# Sitara_IO_Bank_45.net
KiCad netlist of a schematic drawn in Altium Designer
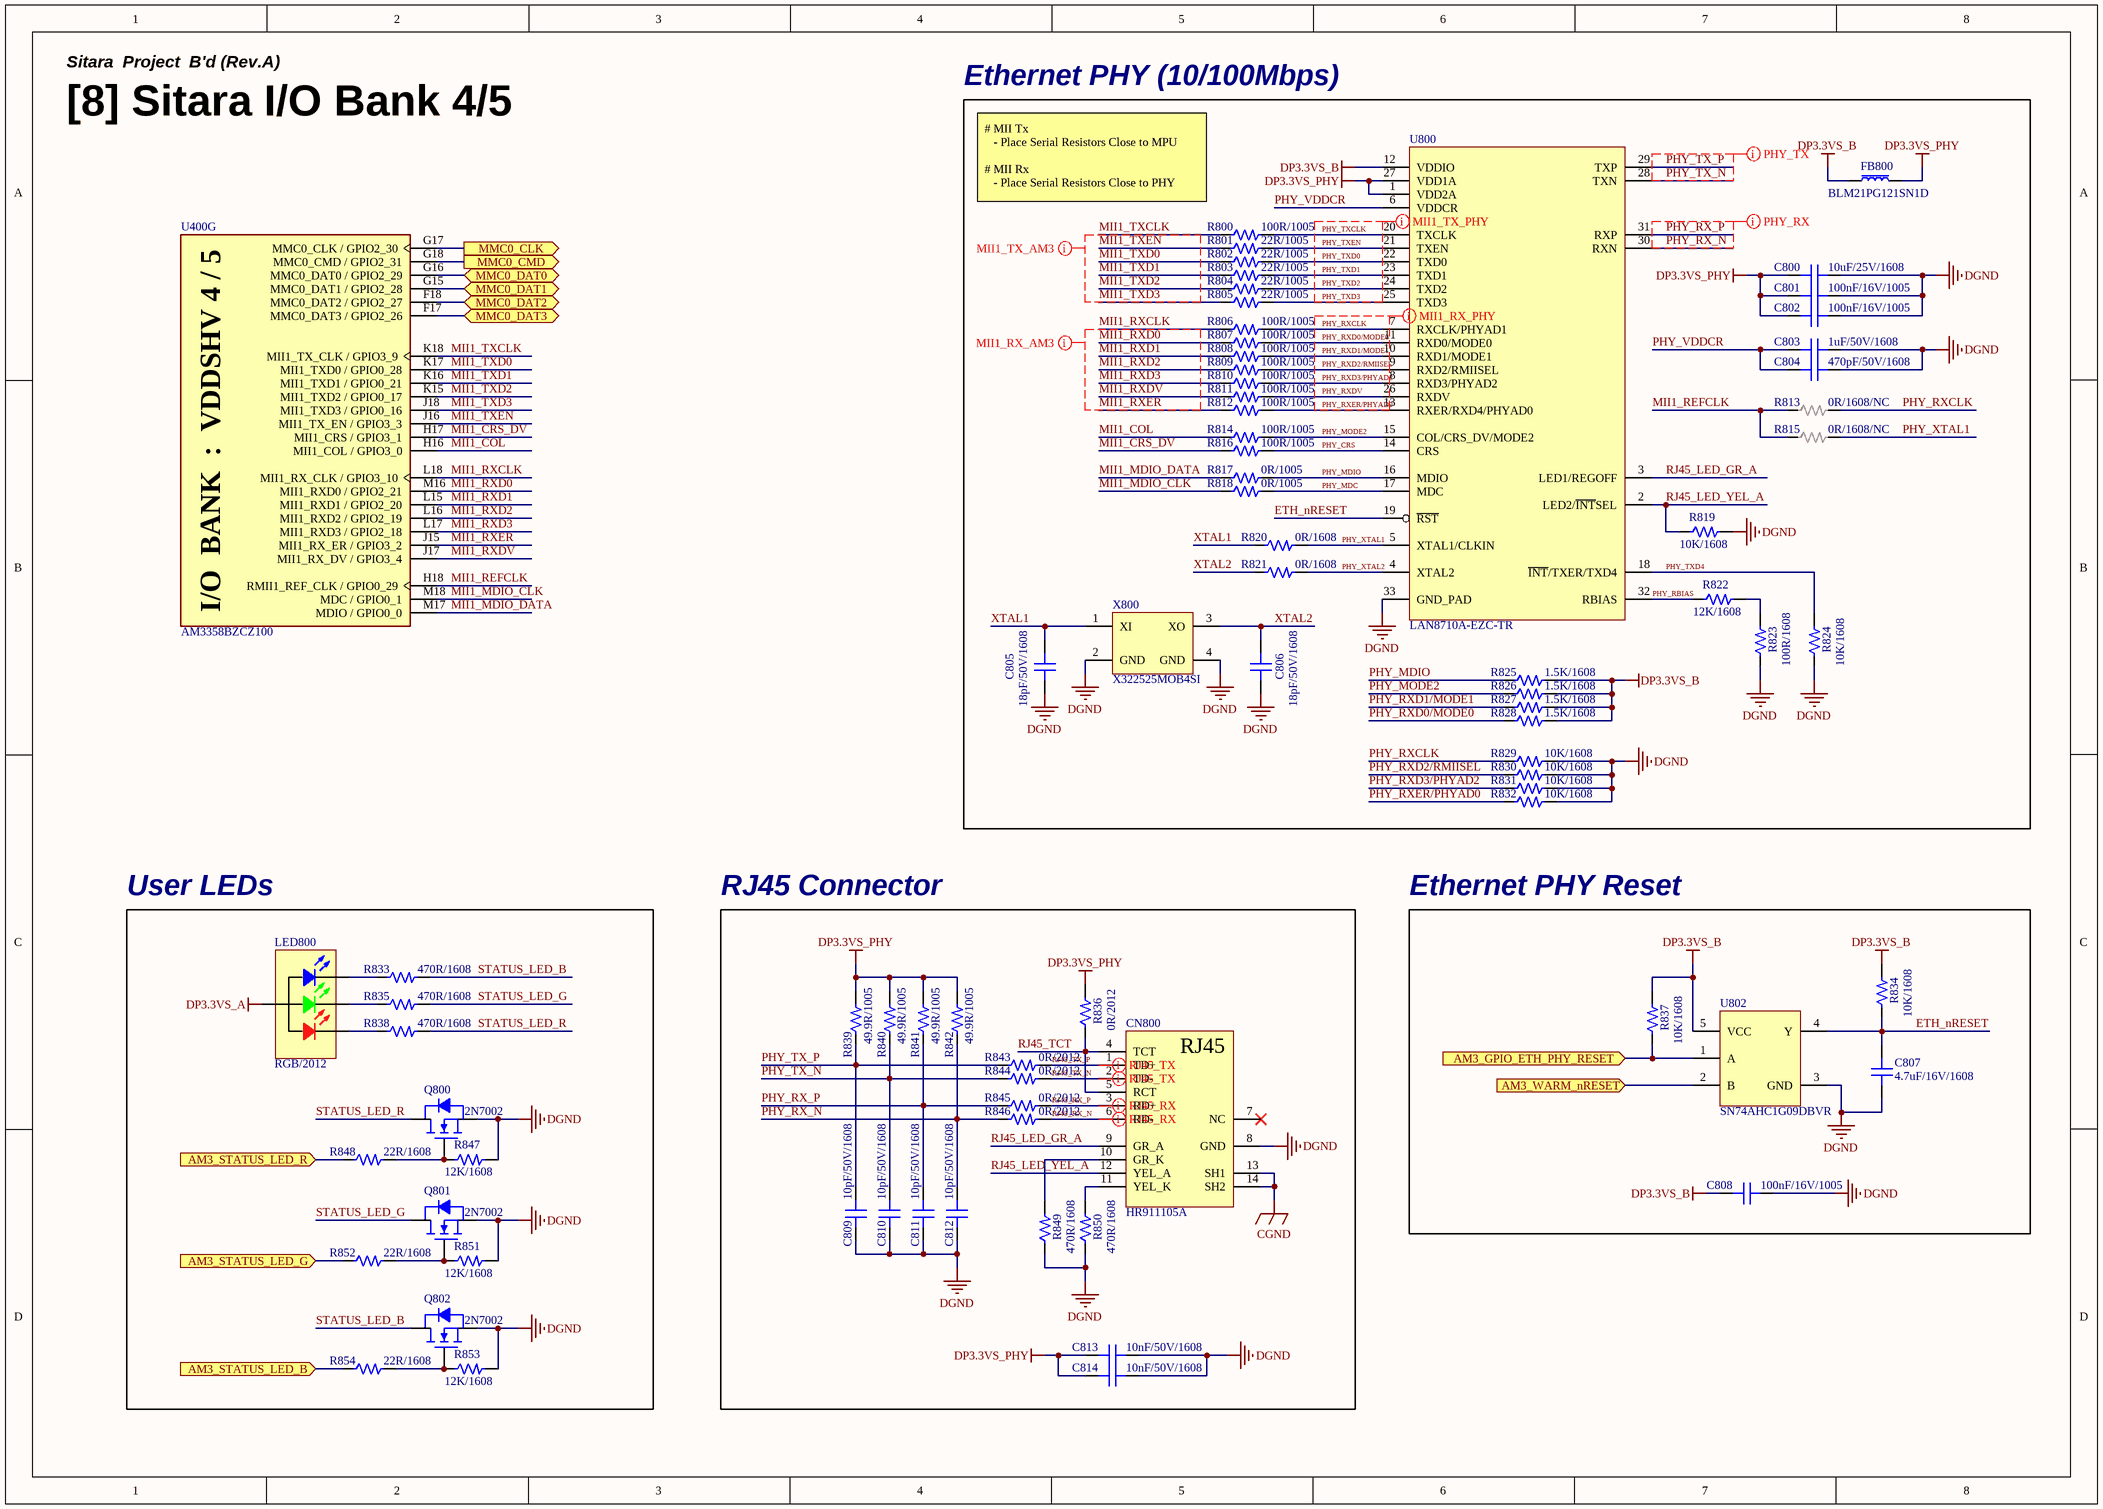
[diagram p0: Sitara_IO_Bank_45.SchDoc]

(export (version "E")
  (design (tool "Eeschema 10.0.6"))
  (components
    (comp (ref "C800")
      (value "10uF/25V/1608")
      (footprint "CAP 1608 (0603_INCH)")
      (description "Ceramic CAP_10uF/25V/1608")
      (fields (field (name "LCSC PART #") "C96446"))
      (libsource (lib "Arkx") (part "CAP_10uF/25V/1608"))
    )
    (comp (ref "C801")
      (value "100nF/16V/1005")
      (footprint "CAP 1005 (0402_INCH)")
      (description "Ceramic CAP_100nF/16V/1005")
      (fields (field (name "LCSC PART #") "C1525"))
      (libsource (lib "Arkx") (part "CAP_100nF/16V/1005"))
    )
    (comp (ref "C802")
      (value "100nF/16V/1005")
      (footprint "CAP 1005 (0402_INCH)")
      (description "Ceramic CAP_100nF/16V/1005")
      (fields (field (name "LCSC PART #") "C1525"))
      (libsource (lib "Arkx") (part "CAP_100nF/16V/1005"))
    )
    (comp (ref "C803")
      (value "1uF/50V/1608")
      (footprint "CAP 1608 (0603_INCH)")
      (description "Ceramic CAP_1uF/50V/1608")
      (fields (field (name "LCSC PART #") "C15849"))
      (libsource (lib "Arkx") (part "CAP_1uF/50V/1608"))
    )
    (comp (ref "C804")
      (value "470pF/50V/1608")
      (footprint "CAP 1608 (0603_INCH)")
      (description "Ceramic CAP_470pF/50V/1608")
      (fields (field (name "LCSC PART #") "C1620"))
      (libsource (lib "Arkx") (part "CAP_470pF/50V/1608"))
    )
    (comp (ref "C805")
      (value "18pF/50V/1608")
      (footprint "CAP 1608 (0603_INCH)")
      (description "Ceramic CAP_18pF/50V/1608")
      (fields (field (name "LCSC PART #") "C1647"))
      (libsource (lib "Arkx") (part "CAP_18pF/50V/1608"))
    )
    (comp (ref "C806")
      (value "18pF/50V/1608")
      (footprint "CAP 1608 (0603_INCH)")
      (description "Ceramic CAP_18pF/50V/1608")
      (fields (field (name "LCSC PART #") "C1647"))
      (libsource (lib "Arkx") (part "CAP_18pF/50V/1608"))
    )
    (comp (ref "C807")
      (value "4.7uF/16V/1608")
      (footprint "CAP 1608 (0603_INCH)")
      (description "Ceramic CAP_4.7uF/16V/1608")
      (fields (field (name "LCSC PART #") "C19666"))
      (libsource (lib "Arkx") (part "CAP_4.7uF/16V/1608"))
    )
    (comp (ref "C808")
      (value "100nF/16V/1005")
      (footprint "CAP 1005 (0402_INCH)")
      (description "Ceramic CAP_100nF/16V/1005")
      (fields (field (name "LCSC PART #") "C1525"))
      (libsource (lib "Arkx") (part "CAP_100nF/16V/1005"))
    )
    (comp (ref "C809")
      (value "10pF/50V/1608")
      (footprint "CAP 1608 (0603_INCH)")
      (description "Ceramic CAP_10pF/50V/1608")
      (fields (field (name "LCSC PART #") "C1634"))
      (libsource (lib "Arkx") (part "CAP_10pF/50V/1608"))
    )
    (comp (ref "C810")
      (value "10pF/50V/1608")
      (footprint "CAP 1608 (0603_INCH)")
      (description "Ceramic CAP_10pF/50V/1608")
      (fields (field (name "LCSC PART #") "C1634"))
      (libsource (lib "Arkx") (part "CAP_10pF/50V/1608"))
    )
    (comp (ref "C811")
      (value "10pF/50V/1608")
      (footprint "CAP 1608 (0603_INCH)")
      (description "Ceramic CAP_10pF/50V/1608")
      (fields (field (name "LCSC PART #") "C1634"))
      (libsource (lib "Arkx") (part "CAP_10pF/50V/1608"))
    )
    (comp (ref "C812")
      (value "10pF/50V/1608")
      (footprint "CAP 1608 (0603_INCH)")
      (description "Ceramic CAP_10pF/50V/1608")
      (fields (field (name "LCSC PART #") "C1634"))
      (libsource (lib "Arkx") (part "CAP_10pF/50V/1608"))
    )
    (comp (ref "C813")
      (value "10nF/50V/1608")
      (footprint "CAP 1608 (0603_INCH)")
      (description "Ceramic CAP_10nF/50V/1608")
      (fields (field (name "LCSC PART #") "C57112"))
      (libsource (lib "Arkx") (part "CAP_10nF/50V/1608"))
    )
    (comp (ref "C814")
      (value "10nF/50V/1608")
      (footprint "CAP 1608 (0603_INCH)")
      (description "Ceramic CAP_10nF/50V/1608")
      (fields (field (name "LCSC PART #") "C57112"))
      (libsource (lib "Arkx") (part "CAP_10nF/50V/1608"))
    )
    (comp (ref "CN800")
      (value "HR911105A")
      (footprint "CON_RJ45")
      (description "RJ45Receptacle 1 WithLED Plugin Ethernet Connectors / Modular Connectors (RJ45 RJ11) ROHS")
      (fields (field (name "LCSC PART #") "C12074"))
      (libsource (lib "Arkx") (part "CON_RJ45_HR911105A"))
    )
    (comp (ref "FB800")
      (value "BLM21PG121SN1D")
      (footprint "FB 2012 (0805_inch)")
      (description "3A 1 30mΩ 120Ω@100MHz ±25% 0805  Ferrite Beads ROHS")
      (fields (field (name "LCSC PART #") "C79382"))
      (libsource (lib "Arkx") (part "FB_BLM21PG121SN1D"))
    )
    (comp (ref "LED800")
      (value "RGB/2012")
      (footprint "LED MHT170RGBCT")
      (fields (field (name "LCSC PART #") "C2962094"))
      (libsource (lib "Arkx") (part "LED_RGB_MHT170RGBCT"))
    )
    (comp (ref "Q800")
      (value "2N7002")
      (footprint "SOT 23-3 (DIODES INCORPORATED)")
      (description "60V 115mA 200mW 7.5Ω@10V,500mA N Channel SOT-23  MOSFETs ROHS")
      (fields (field (name "LCSC PART #") "C8545"))
      (libsource (lib "Arkx") (part "FET_2N7002"))
    )
    (comp (ref "Q801")
      (value "2N7002")
      (footprint "SOT 23-3 (DIODES INCORPORATED)")
      (description "60V 115mA 200mW 7.5Ω@10V,500mA N Channel SOT-23  MOSFETs ROHS")
      (fields (field (name "LCSC PART #") "C8545"))
      (libsource (lib "Arkx") (part "FET_2N7002"))
    )
    (comp (ref "Q802")
      (value "2N7002")
      (footprint "SOT 23-3 (DIODES INCORPORATED)")
      (description "60V 115mA 200mW 7.5Ω@10V,500mA N Channel SOT-23  MOSFETs ROHS")
      (fields (field (name "LCSC PART #") "C8545"))
      (libsource (lib "Arkx") (part "FET_2N7002"))
    )
    (comp (ref "R800")
      (value "100R/1005")
      (footprint "RES 1005 (0402_inch)")
      (description "RES_100R/1005/62.5mW")
      (fields (field (name "LCSC PART #") "C25076"))
      (libsource (lib "Arkx") (part "RES_100R/1005/62.5mW"))
    )
    (comp (ref "R801")
      (value "22R/1005")
      (footprint "RES 1005 (0402_inch)")
      (description "RES_22R/1005/62.5mW")
      (fields (field (name "LCSC PART #") "C25092"))
      (libsource (lib "Arkx") (part "RES_22R/1005/62.5mW"))
    )
    (comp (ref "R802")
      (value "22R/1005")
      (footprint "RES 1005 (0402_inch)")
      (description "RES_22R/1005/62.5mW")
      (fields (field (name "LCSC PART #") "C25092"))
      (libsource (lib "Arkx") (part "RES_22R/1005/62.5mW"))
    )
    (comp (ref "R803")
      (value "22R/1005")
      (footprint "RES 1005 (0402_inch)")
      (description "RES_22R/1005/62.5mW")
      (fields (field (name "LCSC PART #") "C25092"))
      (libsource (lib "Arkx") (part "RES_22R/1005/62.5mW"))
    )
    (comp (ref "R804")
      (value "22R/1005")
      (footprint "RES 1005 (0402_inch)")
      (description "RES_22R/1005/62.5mW")
      (fields (field (name "LCSC PART #") "C25092"))
      (libsource (lib "Arkx") (part "RES_22R/1005/62.5mW"))
    )
    (comp (ref "R805")
      (value "22R/1005")
      (footprint "RES 1005 (0402_inch)")
      (description "RES_22R/1005/62.5mW")
      (fields (field (name "LCSC PART #") "C25092"))
      (libsource (lib "Arkx") (part "RES_22R/1005/62.5mW"))
    )
    (comp (ref "R806")
      (value "100R/1005")
      (footprint "RES 1005 (0402_inch)")
      (description "RES_100R/1005/62.5mW")
      (fields (field (name "LCSC PART #") "C25076"))
      (libsource (lib "Arkx") (part "RES_100R/1005/62.5mW"))
    )
    (comp (ref "R807")
      (value "100R/1005")
      (footprint "RES 1005 (0402_inch)")
      (description "RES_100R/1005/62.5mW")
      (fields (field (name "LCSC PART #") "C25076"))
      (libsource (lib "Arkx") (part "RES_100R/1005/62.5mW"))
    )
    (comp (ref "R808")
      (value "100R/1005")
      (footprint "RES 1005 (0402_inch)")
      (description "RES_100R/1005/62.5mW")
      (fields (field (name "LCSC PART #") "C25076"))
      (libsource (lib "Arkx") (part "RES_100R/1005/62.5mW"))
    )
    (comp (ref "R809")
      (value "100R/1005")
      (footprint "RES 1005 (0402_inch)")
      (description "RES_100R/1005/62.5mW")
      (fields (field (name "LCSC PART #") "C25076"))
      (libsource (lib "Arkx") (part "RES_100R/1005/62.5mW"))
    )
    (comp (ref "R810")
      (value "100R/1005")
      (footprint "RES 1005 (0402_inch)")
      (description "RES_100R/1005/62.5mW")
      (fields (field (name "LCSC PART #") "C25076"))
      (libsource (lib "Arkx") (part "RES_100R/1005/62.5mW"))
    )
    (comp (ref "R811")
      (value "100R/1005")
      (footprint "RES 1005 (0402_inch)")
      (description "RES_100R/1005/62.5mW")
      (fields (field (name "LCSC PART #") "C25076"))
      (libsource (lib "Arkx") (part "RES_100R/1005/62.5mW"))
    )
    (comp (ref "R812")
      (value "100R/1005")
      (footprint "RES 1005 (0402_inch)")
      (description "RES_100R/1005/62.5mW")
      (fields (field (name "LCSC PART #") "C25076"))
      (libsource (lib "Arkx") (part "RES_100R/1005/62.5mW"))
    )
    (comp (ref "R813")
      (value "0R/1608/NC")
      (footprint "RES 1608 (0603_inch)/NC")
      (description "0R/1608/0.1W/NC")
      (libsource (lib "Arkx") (part "RES_NC_0R/1608/0.1W"))
    )
    (comp (ref "R814")
      (value "100R/1005")
      (footprint "RES 1005 (0402_inch)")
      (description "RES_100R/1005/62.5mW")
      (fields (field (name "LCSC PART #") "C25076"))
      (libsource (lib "Arkx") (part "RES_100R/1005/62.5mW"))
    )
    (comp (ref "R815")
      (value "0R/1608/NC")
      (footprint "RES 1608 (0603_inch)/NC")
      (description "0R/1608/0.1W/NC")
      (libsource (lib "Arkx") (part "RES_NC_0R/1608/0.1W"))
    )
    (comp (ref "R816")
      (value "100R/1005")
      (footprint "RES 1005 (0402_inch)")
      (description "RES_100R/1005/62.5mW")
      (fields (field (name "LCSC PART #") "C25076"))
      (libsource (lib "Arkx") (part "RES_100R/1005/62.5mW"))
    )
    (comp (ref "R817")
      (value "0R/1005")
      (footprint "RES 1005 (0402_inch)")
      (description "RES_0R/1005/62.5mW")
      (fields (field (name "LCSC PART #") "C17168"))
      (libsource (lib "Arkx") (part "RES_0R/1005/62.5mW"))
    )
    (comp (ref "R818")
      (value "0R/1005")
      (footprint "RES 1005 (0402_inch)")
      (description "RES_0R/1005/62.5mW")
      (fields (field (name "LCSC PART #") "C17168"))
      (libsource (lib "Arkx") (part "RES_0R/1005/62.5mW"))
    )
    (comp (ref "R819")
      (value "10K/1608")
      (footprint "RES 1608 (0603_inch)")
      (description "RES_10K/1608/0.1W")
      (fields (field (name "LCSC PART #") "C25804"))
      (libsource (lib "Arkx") (part "RES_10K/1608/0.1W"))
    )
    (comp (ref "R820")
      (value "0R/1608")
      (footprint "RES 1608 (0603_inch)")
      (description "RES_0R/1608/0.1W")
      (fields (field (name "LCSC PART #") "C21189"))
      (libsource (lib "Arkx") (part "RES_0R/1608/0.1W"))
    )
    (comp (ref "R821")
      (value "0R/1608")
      (footprint "RES 1608 (0603_inch)")
      (description "RES_0R/1608/0.1W")
      (fields (field (name "LCSC PART #") "C21189"))
      (libsource (lib "Arkx") (part "RES_0R/1608/0.1W"))
    )
    (comp (ref "R822")
      (value "12K/1608")
      (footprint "RES 1608 (0603_inch)")
      (description "RES_12K/1608/0.1W")
      (fields (field (name "LCSC PART #") "C22790"))
      (libsource (lib "Arkx") (part "RES_12K/1608/0.1W"))
    )
    (comp (ref "R823")
      (value "100R/1608")
      (footprint "RES 1608 (0603_inch)")
      (description "RES_100R/1608/0.1W")
      (fields (field (name "LCSC PART #") "C22775"))
      (libsource (lib "Arkx") (part "RES_100R/1608/0.1W"))
    )
    (comp (ref "R824")
      (value "10K/1608")
      (footprint "RES 1608 (0603_inch)")
      (description "RES_10K/1608/0.1W")
      (fields (field (name "LCSC PART #") "C25804"))
      (libsource (lib "Arkx") (part "RES_10K/1608/0.1W"))
    )
    (comp (ref "R825")
      (value "1.5K/1608")
      (footprint "RES 1608 (0603_inch)")
      (description "RES_1.5K/1608/0.1W")
      (fields (field (name "LCSC PART #") "C22843"))
      (libsource (lib "Arkx") (part "RES_1.5K/1608/0.1W"))
    )
    (comp (ref "R826")
      (value "1.5K/1608")
      (footprint "RES 1608 (0603_inch)")
      (description "RES_1.5K/1608/0.1W")
      (fields (field (name "LCSC PART #") "C22843"))
      (libsource (lib "Arkx") (part "RES_1.5K/1608/0.1W"))
    )
    (comp (ref "R827")
      (value "1.5K/1608")
      (footprint "RES 1608 (0603_inch)")
      (description "RES_1.5K/1608/0.1W")
      (fields (field (name "LCSC PART #") "C22843"))
      (libsource (lib "Arkx") (part "RES_1.5K/1608/0.1W"))
    )
    (comp (ref "R828")
      (value "1.5K/1608")
      (footprint "RES 1608 (0603_inch)")
      (description "RES_1.5K/1608/0.1W")
      (fields (field (name "LCSC PART #") "C22843"))
      (libsource (lib "Arkx") (part "RES_1.5K/1608/0.1W"))
    )
    (comp (ref "R829")
      (value "10K/1608")
      (footprint "RES 1608 (0603_inch)")
      (description "RES_10K/1608/0.1W")
      (fields (field (name "LCSC PART #") "C25804"))
      (libsource (lib "Arkx") (part "RES_10K/1608/0.1W"))
    )
    (comp (ref "R830")
      (value "10K/1608")
      (footprint "RES 1608 (0603_inch)")
      (description "RES_10K/1608/0.1W")
      (fields (field (name "LCSC PART #") "C25804"))
      (libsource (lib "Arkx") (part "RES_10K/1608/0.1W"))
    )
    (comp (ref "R831")
      (value "10K/1608")
      (footprint "RES 1608 (0603_inch)")
      (description "RES_10K/1608/0.1W")
      (fields (field (name "LCSC PART #") "C25804"))
      (libsource (lib "Arkx") (part "RES_10K/1608/0.1W"))
    )
    (comp (ref "R832")
      (value "10K/1608")
      (footprint "RES 1608 (0603_inch)")
      (description "RES_10K/1608/0.1W")
      (fields (field (name "LCSC PART #") "C25804"))
      (libsource (lib "Arkx") (part "RES_10K/1608/0.1W"))
    )
    (comp (ref "R833")
      (value "470R/1608")
      (footprint "RES 1608 (0603_inch)")
      (description "RES_470R/1608/0.1W")
      (fields (field (name "LCSC PART #") "C23179"))
      (libsource (lib "Arkx") (part "RES_470R/1608/0.1W"))
    )
    (comp (ref "R834")
      (value "10K/1608")
      (footprint "RES 1608 (0603_inch)")
      (description "RES_10K/1608/0.1W")
      (fields (field (name "LCSC PART #") "C25804"))
      (libsource (lib "Arkx") (part "RES_10K/1608/0.1W"))
    )
    (comp (ref "R835")
      (value "470R/1608")
      (footprint "RES 1608 (0603_inch)")
      (description "RES_470R/1608/0.1W")
      (fields (field (name "LCSC PART #") "C23179"))
      (libsource (lib "Arkx") (part "RES_470R/1608/0.1W"))
    )
    (comp (ref "R836")
      (value "0R/2012")
      (footprint "RES 2012 (0805_inch)")
      (description "RES_0R/2012/0.125W")
      (fields (field (name "LCSC PART #") "C17477"))
      (libsource (lib "Arkx") (part "RES_0R/2012/0.125W"))
    )
    (comp (ref "R837")
      (value "10K/1608")
      (footprint "RES 1608 (0603_inch)")
      (description "RES_10K/1608/0.1W")
      (fields (field (name "LCSC PART #") "C25804"))
      (libsource (lib "Arkx") (part "RES_10K/1608/0.1W"))
    )
    (comp (ref "R838")
      (value "470R/1608")
      (footprint "RES 1608 (0603_inch)")
      (description "RES_470R/1608/0.1W")
      (fields (field (name "LCSC PART #") "C23179"))
      (libsource (lib "Arkx") (part "RES_470R/1608/0.1W"))
    )
    (comp (ref "R839")
      (value "49.9R/1005")
      (footprint "RES 1005 (0402_inch)")
      (description "RES_49.9R/1005/62.5mW")
      (fields (field (name "LCSC PART #") "C25120"))
      (libsource (lib "Arkx") (part "RES_49.9R/1005/62.5mW"))
    )
    (comp (ref "R840")
      (value "49.9R/1005")
      (footprint "RES 1005 (0402_inch)")
      (description "RES_49.9R/1005/62.5mW")
      (fields (field (name "LCSC PART #") "C25120"))
      (libsource (lib "Arkx") (part "RES_49.9R/1005/62.5mW"))
    )
    (comp (ref "R841")
      (value "49.9R/1005")
      (footprint "RES 1005 (0402_inch)")
      (description "RES_49.9R/1005/62.5mW")
      (fields (field (name "LCSC PART #") "C25120"))
      (libsource (lib "Arkx") (part "RES_49.9R/1005/62.5mW"))
    )
    (comp (ref "R842")
      (value "49.9R/1005")
      (footprint "RES 1005 (0402_inch)")
      (description "RES_49.9R/1005/62.5mW")
      (fields (field (name "LCSC PART #") "C25120"))
      (libsource (lib "Arkx") (part "RES_49.9R/1005/62.5mW"))
    )
    (comp (ref "R843")
      (value "0R/2012")
      (footprint "RES 2012 (0805_inch)")
      (description "RES_0R/2012/0.125W")
      (fields (field (name "LCSC PART #") "C17477"))
      (libsource (lib "Arkx") (part "RES_0R/2012/0.125W"))
    )
    (comp (ref "R844")
      (value "0R/2012")
      (footprint "RES 2012 (0805_inch)")
      (description "RES_0R/2012/0.125W")
      (fields (field (name "LCSC PART #") "C17477"))
      (libsource (lib "Arkx") (part "RES_0R/2012/0.125W"))
    )
    (comp (ref "R845")
      (value "0R/2012")
      (footprint "RES 2012 (0805_inch)")
      (description "RES_0R/2012/0.125W")
      (fields (field (name "LCSC PART #") "C17477"))
      (libsource (lib "Arkx") (part "RES_0R/2012/0.125W"))
    )
    (comp (ref "R846")
      (value "0R/2012")
      (footprint "RES 2012 (0805_inch)")
      (description "RES_0R/2012/0.125W")
      (fields (field (name "LCSC PART #") "C17477"))
      (libsource (lib "Arkx") (part "RES_0R/2012/0.125W"))
    )
    (comp (ref "R847")
      (value "12K/1608")
      (footprint "RES 1608 (0603_inch)")
      (description "RES_12K/1608/0.1W")
      (fields (field (name "LCSC PART #") "C22790"))
      (libsource (lib "Arkx") (part "RES_12K/1608/0.1W"))
    )
    (comp (ref "R848")
      (value "22R/1608")
      (footprint "RES 1608 (0603_inch)")
      (description "RES_22R/1608/0.1W")
      (fields (field (name "LCSC PART #") "C23345"))
      (libsource (lib "Arkx") (part "RES_22R/1608/0.1W"))
    )
    (comp (ref "R849")
      (value "470R/1608")
      (footprint "RES 1608 (0603_inch)")
      (description "RES_470R/1608/0.1W")
      (fields (field (name "LCSC PART #") "C23179"))
      (libsource (lib "Arkx") (part "RES_470R/1608/0.1W"))
    )
    (comp (ref "R850")
      (value "470R/1608")
      (footprint "RES 1608 (0603_inch)")
      (description "RES_470R/1608/0.1W")
      (fields (field (name "LCSC PART #") "C23179"))
      (libsource (lib "Arkx") (part "RES_470R/1608/0.1W"))
    )
    (comp (ref "R851")
      (value "12K/1608")
      (footprint "RES 1608 (0603_inch)")
      (description "RES_12K/1608/0.1W")
      (fields (field (name "LCSC PART #") "C22790"))
      (libsource (lib "Arkx") (part "RES_12K/1608/0.1W"))
    )
    (comp (ref "R852")
      (value "22R/1608")
      (footprint "RES 1608 (0603_inch)")
      (description "RES_22R/1608/0.1W")
      (fields (field (name "LCSC PART #") "C23345"))
      (libsource (lib "Arkx") (part "RES_22R/1608/0.1W"))
    )
    (comp (ref "R853")
      (value "12K/1608")
      (footprint "RES 1608 (0603_inch)")
      (description "RES_12K/1608/0.1W")
      (fields (field (name "LCSC PART #") "C22790"))
      (libsource (lib "Arkx") (part "RES_12K/1608/0.1W"))
    )
    (comp (ref "R854")
      (value "22R/1608")
      (footprint "RES 1608 (0603_inch)")
      (description "RES_22R/1608/0.1W")
      (fields (field (name "LCSC PART #") "C23345"))
      (libsource (lib "Arkx") (part "RES_22R/1608/0.1W"))
    )
    (comp (ref "U400")
      (value "AM3358BZCZ100")
      (footprint "IC_SOC_AM3358BZCZ100")
      (description "ARM® Cortex®-A8 Microprocessor IC Sitara™ 1 Core, 32-Bit 1.0GHz 324-NFBGA (15x15)")
      (fields (field (name "LCSC PART #") "C73932"))
      (libsource (lib "Arkx") (part "IC_SOC_AM3358BZCZ100"))
    )
    (comp (ref "U800")
      (value "LAN8710A-EZC-TR")
      (footprint "IC_QFN-32 (5x5)")
      (description "4/4 Transceiver Full MII, RMII 32-QFN (5x5)")
      (fields (field (name "LCSC PART #") "C46185"))
      (libsource (lib "Arkx") (part "IC_ETH_LAN8710A-EZC-TR"))
    )
    (comp (ref "U802")
      (value "SN74AHC1G09DBVR")
      (footprint "SOT-23-5 (TI DBV PACKAGE)")
      (description "AND Gate IC 1 Channel Open Drain SOT-23-5")
      (fields (field (name "LCSC PART #") "C840099"))
      (libsource (lib "Arkx") (part "IC_AND_SN74AHC1G09DBVR"))
    )
    (comp (ref "X800")
      (value "X322525MOB4SI")
      (footprint "OSC_SMD_3.2x2.5(YXC)")
      (description "25MHz Surface Mount Crystal 12pF ±10ppm ±20ppm SMD3225-4P Crystals ROHS")
      (fields (field (name "LCSC PART #") "C9006"))
      (libsource (lib "Arkx") (part "XTAL_25MHz_X322525MOB4SI"))
    )
  )
  (nets
    (net (code "1") (name "/AM3_GPIO_ETH_PHY_RESET") (class "Default")
      (node (ref "R837") (pin "1") (pinfunction "1_1") (pintype "passive"))
      (node (ref "U802") (pin "1") (pinfunction "A_1") (pintype "passive"))
    )
    (net (code "2") (name "/AM3_STATUS_LED_B") (class "Default")
      (node (ref "R854") (pin "1") (pinfunction "1_1") (pintype "passive"))
    )
    (net (code "3") (name "/AM3_STATUS_LED_G") (class "Default")
      (node (ref "R852") (pin "1") (pinfunction "1_1") (pintype "passive"))
    )
    (net (code "4") (name "/AM3_STATUS_LED_R") (class "Default")
      (node (ref "R848") (pin "1") (pinfunction "1_1") (pintype "passive"))
    )
    (net (code "5") (name "/AM3_WARM_nRESET") (class "Default")
      (node (ref "U802") (pin "2") (pinfunction "B_2") (pintype "passive"))
    )
    (net (code "6") (name "/ETH_nRESET") (class "Default")
      (node (ref "C807") (pin "2") (pinfunction "2_2") (pintype "passive"))
      (node (ref "R834") (pin "1") (pinfunction "1_1") (pintype "passive"))
      (node (ref "U800") (pin "19") (pinfunction "~{RST}_19") (pintype "passive"))
      (node (ref "U802") (pin "4") (pinfunction "Y_4") (pintype "passive"))
    )
    (net (code "7") (name "/MII1_COL") (class "Default")
      (node (ref "R814") (pin "1") (pinfunction "1_1") (pintype "passive"))
      (node (ref "U400") (pin "H16") (pinfunction "MII1_COL_/_GPIO3_0_H16") (pintype "passive"))
    )
    (net (code "8") (name "/MII1_CRS_DV") (class "Default")
      (node (ref "R816") (pin "1") (pinfunction "1_1") (pintype "passive"))
      (node (ref "U400") (pin "H17") (pinfunction "MII1_CRS_/_GPIO3_1_H17") (pintype "passive"))
    )
    (net (code "9") (name "/MII1_MDIO_CLK") (class "Default")
      (node (ref "R818") (pin "1") (pinfunction "1_1") (pintype "passive"))
      (node (ref "U400") (pin "M18") (pinfunction "MDC_/_GPIO0_1_M18") (pintype "passive"))
    )
    (net (code "10") (name "/MII1_MDIO_DATA") (class "Default")
      (node (ref "R817") (pin "1") (pinfunction "1_1") (pintype "passive"))
      (node (ref "U400") (pin "M17") (pinfunction "MDIO_/_GPIO0_0_M17") (pintype "passive"))
    )
    (net (code "11") (name "/MII1_REFCLK") (class "Default")
      (node (ref "R813") (pin "1") (pinfunction "1_1") (pintype "passive"))
      (node (ref "R815") (pin "1") (pinfunction "1_1") (pintype "passive"))
      (node (ref "U400") (pin "H18") (pinfunction "RMII1_REF_CLK_/_GPIO0_29_H18") (pintype "passive"))
    )
    (net (code "12") (name "/MII1_RXCLK") (class "Default")
      (node (ref "R806") (pin "1") (pinfunction "1_1") (pintype "passive"))
      (node (ref "U400") (pin "L18") (pinfunction "MII1_RX_CLK_/_GPIO3_10_L18") (pintype "passive"))
    )
    (net (code "13") (name "/MII1_RXD0") (class "Default")
      (node (ref "R807") (pin "1") (pinfunction "1_1") (pintype "passive"))
      (node (ref "U400") (pin "M16") (pinfunction "MII1_RXD0_/_GPIO2_21_M16") (pintype "passive"))
    )
    (net (code "14") (name "/MII1_RXD1") (class "Default")
      (node (ref "R808") (pin "1") (pinfunction "1_1") (pintype "passive"))
      (node (ref "U400") (pin "L15") (pinfunction "MII1_RXD1_/_GPIO2_20_L15") (pintype "passive"))
    )
    (net (code "15") (name "/MII1_RXD2") (class "Default")
      (node (ref "R809") (pin "1") (pinfunction "1_1") (pintype "passive"))
      (node (ref "U400") (pin "L16") (pinfunction "MII1_RXD2_/_GPIO2_19_L16") (pintype "passive"))
    )
    (net (code "16") (name "/MII1_RXD3") (class "Default")
      (node (ref "R810") (pin "1") (pinfunction "1_1") (pintype "passive"))
      (node (ref "U400") (pin "L17") (pinfunction "MII1_RXD3_/_GPIO2_18_L17") (pintype "passive"))
    )
    (net (code "17") (name "/MII1_RXDV") (class "Default")
      (node (ref "R811") (pin "1") (pinfunction "1_1") (pintype "passive"))
      (node (ref "U400") (pin "J17") (pinfunction "MII1_RX_DV_/_GPIO3_4_J17") (pintype "passive"))
    )
    (net (code "18") (name "/MII1_RXER") (class "Default")
      (node (ref "R812") (pin "1") (pinfunction "1_1") (pintype "passive"))
      (node (ref "U400") (pin "J15") (pinfunction "MII1_RX_ER_/_GPIO3_2_J15") (pintype "passive"))
    )
    (net (code "19") (name "/MII1_TXCLK") (class "Default")
      (node (ref "R800") (pin "1") (pinfunction "1_1") (pintype "passive"))
      (node (ref "U400") (pin "K18") (pinfunction "MII1_TX_CLK_/_GPIO3_9_K18") (pintype "passive"))
    )
    (net (code "20") (name "/MII1_TXD0") (class "Default")
      (node (ref "R802") (pin "1") (pinfunction "1_1") (pintype "passive"))
      (node (ref "U400") (pin "K17") (pinfunction "MII1_TXD0_/_GPIO0_28_K17") (pintype "passive"))
    )
    (net (code "21") (name "/MII1_TXD1") (class "Default")
      (node (ref "R803") (pin "1") (pinfunction "1_1") (pintype "passive"))
      (node (ref "U400") (pin "K16") (pinfunction "MII1_TXD1_/_GPIO0_21_K16") (pintype "passive"))
    )
    (net (code "22") (name "/MII1_TXD2") (class "Default")
      (node (ref "R804") (pin "1") (pinfunction "1_1") (pintype "passive"))
      (node (ref "U400") (pin "K15") (pinfunction "MII1_TXD2_/_GPIO0_17_K15") (pintype "passive"))
    )
    (net (code "23") (name "/MII1_TXD3") (class "Default")
      (node (ref "R805") (pin "1") (pinfunction "1_1") (pintype "passive"))
      (node (ref "U400") (pin "J18") (pinfunction "MII1_TXD3_/_GPIO0_16_J18") (pintype "passive"))
    )
    (net (code "24") (name "/MII1_TXEN") (class "Default")
      (node (ref "R801") (pin "1") (pinfunction "1_1") (pintype "passive"))
      (node (ref "U400") (pin "J16") (pinfunction "MII1_TX_EN_/_GPIO3_3_J16") (pintype "passive"))
    )
    (net (code "25") (name "/MMC0_CLK") (class "Default")
      (node (ref "U400") (pin "G17") (pinfunction "MMC0_CLK_/_GPIO2_30_G17") (pintype "passive"))
    )
    (net (code "26") (name "/MMC0_CMD") (class "Default")
      (node (ref "U400") (pin "G18") (pinfunction "MMC0_CMD_/_GPIO2_31_G18") (pintype "passive"))
    )
    (net (code "27") (name "/MMC0_DAT0") (class "Default")
      (node (ref "U400") (pin "G16") (pinfunction "MMC0_DAT0_/_GPIO2_29_G16") (pintype "passive"))
    )
    (net (code "28") (name "/MMC0_DAT1") (class "Default")
      (node (ref "U400") (pin "G15") (pinfunction "MMC0_DAT1_/_GPIO2_28_G15") (pintype "passive"))
    )
    (net (code "29") (name "/MMC0_DAT2") (class "Default")
      (node (ref "U400") (pin "F18") (pinfunction "MMC0_DAT2_/_GPIO2_27_F18") (pintype "passive"))
    )
    (net (code "30") (name "/MMC0_DAT3") (class "Default")
      (node (ref "U400") (pin "F17") (pinfunction "MMC0_DAT3_/_GPIO2_26_F17") (pintype "passive"))
    )
    (net (code "31") (name "/PHY_CRS") (class "Default")
      (node (ref "R816") (pin "2") (pinfunction "2_2") (pintype "passive"))
      (node (ref "U800") (pin "14") (pinfunction "CRS_14") (pintype "passive"))
    )
    (net (code "32") (name "/PHY_MDC") (class "Default")
      (node (ref "R818") (pin "2") (pinfunction "2_2") (pintype "passive"))
      (node (ref "U800") (pin "17") (pinfunction "MDC_17") (pintype "passive"))
    )
    (net (code "33") (name "/PHY_MDIO") (class "Default")
      (node (ref "R817") (pin "2") (pinfunction "2_2") (pintype "passive"))
      (node (ref "R825") (pin "1") (pinfunction "1_1") (pintype "passive"))
      (node (ref "U800") (pin "16") (pinfunction "MDIO_16") (pintype "passive"))
    )
    (net (code "34") (name "/PHY_MODE2") (class "Default")
      (node (ref "R814") (pin "2") (pinfunction "2_2") (pintype "passive"))
      (node (ref "R826") (pin "1") (pinfunction "1_1") (pintype "passive"))
      (node (ref "U800") (pin "15") (pinfunction "COL/CRS_DV/MODE2_15") (pintype "passive"))
    )
    (net (code "35") (name "/PHY_RBIAS") (class "Default")
      (node (ref "R822") (pin "1") (pinfunction "1_1") (pintype "passive"))
      (node (ref "U800") (pin "32") (pinfunction "RBIAS_32") (pintype "passive"))
    )
    (net (code "36") (name "/PHY_RXCLK") (class "Default")
      (node (ref "R806") (pin "2") (pinfunction "2_2") (pintype "passive"))
      (node (ref "R813") (pin "2") (pinfunction "2_2") (pintype "passive"))
      (node (ref "R829") (pin "1") (pinfunction "1_1") (pintype "passive"))
      (node (ref "U800") (pin "7") (pinfunction "RXCLK/PHYAD1_7") (pintype "passive"))
    )
    (net (code "37") (name "/PHY_RXD0{slash}MODE0") (class "Default")
      (node (ref "R807") (pin "2") (pinfunction "2_2") (pintype "passive"))
      (node (ref "R828") (pin "1") (pinfunction "1_1") (pintype "passive"))
      (node (ref "U800") (pin "11") (pinfunction "RXD0/MODE0_11") (pintype "passive"))
    )
    (net (code "38") (name "/PHY_RXD1{slash}MODE1") (class "Default")
      (node (ref "R808") (pin "2") (pinfunction "2_2") (pintype "passive"))
      (node (ref "R827") (pin "1") (pinfunction "1_1") (pintype "passive"))
      (node (ref "U800") (pin "10") (pinfunction "RXD1/MODE1_10") (pintype "passive"))
    )
    (net (code "39") (name "/PHY_RXD2{slash}RMIISEL") (class "Default")
      (node (ref "R809") (pin "2") (pinfunction "2_2") (pintype "passive"))
      (node (ref "R830") (pin "1") (pinfunction "1_1") (pintype "passive"))
      (node (ref "U800") (pin "9") (pinfunction "RXD2/RMIISEL_9") (pintype "passive"))
    )
    (net (code "40") (name "/PHY_RXD3{slash}PHYAD2") (class "Default")
      (node (ref "R810") (pin "2") (pinfunction "2_2") (pintype "passive"))
      (node (ref "R831") (pin "1") (pinfunction "1_1") (pintype "passive"))
      (node (ref "U800") (pin "8") (pinfunction "RXD3/PHYAD2_8") (pintype "passive"))
    )
    (net (code "41") (name "/PHY_RXDV") (class "Default")
      (node (ref "R811") (pin "2") (pinfunction "2_2") (pintype "passive"))
      (node (ref "U800") (pin "26") (pinfunction "RXDV_26") (pintype "passive"))
    )
    (net (code "42") (name "/PHY_RXER{slash}PHYAD0") (class "Default")
      (node (ref "R812") (pin "2") (pinfunction "2_2") (pintype "passive"))
      (node (ref "R832") (pin "1") (pinfunction "1_1") (pintype "passive"))
      (node (ref "U800") (pin "13") (pinfunction "RXER/RXD4/PHYAD0_13") (pintype "passive"))
    )
    (net (code "43") (name "/PHY_RX_N") (class "Default")
      (node (ref "C812") (pin "2") (pinfunction "2_2") (pintype "passive"))
      (node (ref "R842") (pin "1") (pinfunction "1_1") (pintype "passive"))
      (node (ref "R846") (pin "1") (pinfunction "1_1") (pintype "passive"))
      (node (ref "U800") (pin "30") (pinfunction "RXN_30") (pintype "passive"))
    )
    (net (code "44") (name "/PHY_RX_P") (class "Default")
      (node (ref "C811") (pin "2") (pinfunction "2_2") (pintype "passive"))
      (node (ref "R841") (pin "1") (pinfunction "1_1") (pintype "passive"))
      (node (ref "R845") (pin "1") (pinfunction "1_1") (pintype "passive"))
      (node (ref "U800") (pin "31") (pinfunction "RXP_31") (pintype "passive"))
    )
    (net (code "45") (name "/PHY_TXCLK") (class "Default")
      (node (ref "R800") (pin "2") (pinfunction "2_2") (pintype "passive"))
      (node (ref "U800") (pin "20") (pinfunction "TXCLK_20") (pintype "passive"))
    )
    (net (code "46") (name "/PHY_TXD0") (class "Default")
      (node (ref "R802") (pin "2") (pinfunction "2_2") (pintype "passive"))
      (node (ref "U800") (pin "22") (pinfunction "TXD0_22") (pintype "passive"))
    )
    (net (code "47") (name "/PHY_TXD1") (class "Default")
      (node (ref "R803") (pin "2") (pinfunction "2_2") (pintype "passive"))
      (node (ref "U800") (pin "23") (pinfunction "TXD1_23") (pintype "passive"))
    )
    (net (code "48") (name "/PHY_TXD2") (class "Default")
      (node (ref "R804") (pin "2") (pinfunction "2_2") (pintype "passive"))
      (node (ref "U800") (pin "24") (pinfunction "TXD2_24") (pintype "passive"))
    )
    (net (code "49") (name "/PHY_TXD3") (class "Default")
      (node (ref "R805") (pin "2") (pinfunction "2_2") (pintype "passive"))
      (node (ref "U800") (pin "25") (pinfunction "TXD3_25") (pintype "passive"))
    )
    (net (code "50") (name "/PHY_TXD4") (class "Default")
      (node (ref "R824") (pin "2") (pinfunction "2_2") (pintype "passive"))
      (node (ref "U800") (pin "18") (pinfunction "~{INT}/TXER/TXD4_18") (pintype "passive"))
    )
    (net (code "51") (name "/PHY_TXEN") (class "Default")
      (node (ref "R801") (pin "2") (pinfunction "2_2") (pintype "passive"))
      (node (ref "U800") (pin "21") (pinfunction "TXEN_21") (pintype "passive"))
    )
    (net (code "52") (name "/PHY_TX_N") (class "Default")
      (node (ref "C810") (pin "2") (pinfunction "2_2") (pintype "passive"))
      (node (ref "R840") (pin "1") (pinfunction "1_1") (pintype "passive"))
      (node (ref "R844") (pin "1") (pinfunction "1_1") (pintype "passive"))
      (node (ref "U800") (pin "28") (pinfunction "TXN_28") (pintype "passive"))
    )
    (net (code "53") (name "/PHY_TX_P") (class "Default")
      (node (ref "C809") (pin "2") (pinfunction "2_2") (pintype "passive"))
      (node (ref "R839") (pin "1") (pinfunction "1_1") (pintype "passive"))
      (node (ref "R843") (pin "1") (pinfunction "1_1") (pintype "passive"))
      (node (ref "U800") (pin "29") (pinfunction "TXP_29") (pintype "passive"))
    )
    (net (code "54") (name "/PHY_VDDCR") (class "Default")
      (node (ref "C803") (pin "1") (pinfunction "1_1") (pintype "passive"))
      (node (ref "C804") (pin "1") (pinfunction "1_1") (pintype "passive"))
      (node (ref "U800") (pin "6") (pinfunction "VDDCR_6") (pintype "passive"))
    )
    (net (code "55") (name "/PHY_XTAL1") (class "Default")
      (node (ref "R815") (pin "2") (pinfunction "2_2") (pintype "passive"))
      (node (ref "R820") (pin "2") (pinfunction "2_2") (pintype "passive"))
      (node (ref "U800") (pin "5") (pinfunction "XTAL1/CLKIN_5") (pintype "passive"))
    )
    (net (code "56") (name "/PHY_XTAL2") (class "Default")
      (node (ref "R821") (pin "2") (pinfunction "2_2") (pintype "passive"))
      (node (ref "U800") (pin "4") (pinfunction "XTAL2_4") (pintype "passive"))
    )
    (net (code "57") (name "/RJ45_LED_GR_A") (class "Default")
      (node (ref "CN800") (pin "9") (pinfunction "GR_A_9") (pintype "passive"))
      (node (ref "U800") (pin "3") (pinfunction "LED1/REGOFF_3") (pintype "passive"))
    )
    (net (code "58") (name "/RJ45_LED_YEL_A") (class "Default")
      (node (ref "CN800") (pin "12") (pinfunction "YEL_A_12") (pintype "passive"))
      (node (ref "R819") (pin "1") (pinfunction "1_1") (pintype "passive"))
      (node (ref "U800") (pin "2") (pinfunction "LED2/~{INT}SEL_2") (pintype "passive"))
    )
    (net (code "59") (name "/RJ45_RX_N") (class "Default")
      (node (ref "CN800") (pin "6") (pinfunction "RD-_6") (pintype "passive"))
      (node (ref "R846") (pin "2") (pinfunction "2_2") (pintype "passive"))
    )
    (net (code "60") (name "/RJ45_RX_P") (class "Default")
      (node (ref "CN800") (pin "3") (pinfunction "RD+_3") (pintype "passive"))
      (node (ref "R845") (pin "2") (pinfunction "2_2") (pintype "passive"))
    )
    (net (code "61") (name "/RJ45_TCT") (class "Default")
      (node (ref "CN800") (pin "4") (pinfunction "TCT_4") (pintype "passive"))
      (node (ref "CN800") (pin "5") (pinfunction "RCT_5") (pintype "passive"))
      (node (ref "R836") (pin "1") (pinfunction "1_1") (pintype "passive"))
    )
    (net (code "62") (name "/RJ45_TX_N") (class "Default")
      (node (ref "CN800") (pin "2") (pinfunction "TD-_2") (pintype "passive"))
      (node (ref "R844") (pin "2") (pinfunction "2_2") (pintype "passive"))
    )
    (net (code "63") (name "/RJ45_TX_P") (class "Default")
      (node (ref "CN800") (pin "1") (pinfunction "TD+_1") (pintype "passive"))
      (node (ref "R843") (pin "2") (pinfunction "2_2") (pintype "passive"))
    )
    (net (code "64") (name "/STATUS_LED_B") (class "Default")
      (node (ref "Q802") (pin "3") (pinfunction "D_3") (pintype "passive"))
      (node (ref "R833") (pin "2") (pinfunction "2_2") (pintype "passive"))
    )
    (net (code "65") (name "/STATUS_LED_G") (class "Default")
      (node (ref "Q801") (pin "3") (pinfunction "D_3") (pintype "passive"))
      (node (ref "R835") (pin "2") (pinfunction "2_2") (pintype "passive"))
    )
    (net (code "66") (name "/STATUS_LED_R") (class "Default")
      (node (ref "Q800") (pin "3") (pinfunction "D_3") (pintype "passive"))
      (node (ref "R838") (pin "2") (pinfunction "2_2") (pintype "passive"))
    )
    (net (code "67") (name "/XTAL1") (class "Default")
      (node (ref "C805") (pin "2") (pinfunction "2_2") (pintype "passive"))
      (node (ref "R820") (pin "1") (pinfunction "1_1") (pintype "passive"))
      (node (ref "X800") (pin "1") (pinfunction "XI_1") (pintype "passive"))
    )
    (net (code "68") (name "/XTAL2") (class "Default")
      (node (ref "C806") (pin "2") (pinfunction "2_2") (pintype "passive"))
      (node (ref "R821") (pin "1") (pinfunction "1_1") (pintype "passive"))
      (node (ref "X800") (pin "3") (pinfunction "XO_3") (pintype "passive"))
    )
    (net (code "69") (name "CGND") (class "Default")
      (node (ref "CN800") (pin "13") (pinfunction "SH1_13") (pintype "passive"))
      (node (ref "CN800") (pin "14") (pinfunction "SH2_14") (pintype "passive"))
    )
    (net (code "70") (name "DGND") (class "Default")
      (node (ref "C800") (pin "2") (pinfunction "2_2") (pintype "passive"))
      (node (ref "C801") (pin "2") (pinfunction "2_2") (pintype "passive"))
      (node (ref "C802") (pin "2") (pinfunction "2_2") (pintype "passive"))
      (node (ref "C803") (pin "2") (pinfunction "2_2") (pintype "passive"))
      (node (ref "C804") (pin "2") (pinfunction "2_2") (pintype "passive"))
      (node (ref "C805") (pin "1") (pinfunction "1_1") (pintype "passive"))
      (node (ref "C806") (pin "1") (pinfunction "1_1") (pintype "passive"))
      (node (ref "C807") (pin "1") (pinfunction "1_1") (pintype "passive"))
      (node (ref "C808") (pin "1") (pinfunction "1_1") (pintype "passive"))
      (node (ref "C809") (pin "1") (pinfunction "1_1") (pintype "passive"))
      (node (ref "C810") (pin "1") (pinfunction "1_1") (pintype "passive"))
      (node (ref "C811") (pin "1") (pinfunction "1_1") (pintype "passive"))
      (node (ref "C812") (pin "1") (pinfunction "1_1") (pintype "passive"))
      (node (ref "C813") (pin "2") (pinfunction "2_2") (pintype "passive"))
      (node (ref "C814") (pin "2") (pinfunction "2_2") (pintype "passive"))
      (node (ref "CN800") (pin "8") (pinfunction "GND_8") (pintype "passive"))
      (node (ref "Q800") (pin "2") (pinfunction "S_2") (pintype "passive"))
      (node (ref "Q801") (pin "2") (pinfunction "S_2") (pintype "passive"))
      (node (ref "Q802") (pin "2") (pinfunction "S_2") (pintype "passive"))
      (node (ref "R819") (pin "2") (pinfunction "2_2") (pintype "passive"))
      (node (ref "R823") (pin "1") (pinfunction "1_1") (pintype "passive"))
      (node (ref "R824") (pin "1") (pinfunction "1_1") (pintype "passive"))
      (node (ref "R829") (pin "2") (pinfunction "2_2") (pintype "passive"))
      (node (ref "R830") (pin "2") (pinfunction "2_2") (pintype "passive"))
      (node (ref "R831") (pin "2") (pinfunction "2_2") (pintype "passive"))
      (node (ref "R832") (pin "2") (pinfunction "2_2") (pintype "passive"))
      (node (ref "R847") (pin "2") (pinfunction "2_2") (pintype "passive"))
      (node (ref "R849") (pin "1") (pinfunction "1_1") (pintype "passive"))
      (node (ref "R850") (pin "1") (pinfunction "1_1") (pintype "passive"))
      (node (ref "R851") (pin "2") (pinfunction "2_2") (pintype "passive"))
      (node (ref "R853") (pin "2") (pinfunction "2_2") (pintype "passive"))
      (node (ref "U800") (pin "33") (pinfunction "GND_PAD_33") (pintype "passive"))
      (node (ref "U802") (pin "3") (pinfunction "GND_3") (pintype "passive"))
      (node (ref "X800") (pin "2") (pinfunction "GND_2") (pintype "passive"))
      (node (ref "X800") (pin "4") (pinfunction "GND_4") (pintype "passive"))
    )
    (net (code "71") (name "DP3.3VS_A") (class "Default")
      (node (ref "LED800") (pin "4") (pinfunction "Common_Anode_4") (pintype "passive"))
    )
    (net (code "72") (name "DP3.3VS_B") (class "Default")
      (node (ref "C808") (pin "2") (pinfunction "2_2") (pintype "passive"))
      (node (ref "FB800") (pin "1") (pinfunction "1_1") (pintype "passive"))
      (node (ref "R825") (pin "2") (pinfunction "2_2") (pintype "passive"))
      (node (ref "R826") (pin "2") (pinfunction "2_2") (pintype "passive"))
      (node (ref "R827") (pin "2") (pinfunction "2_2") (pintype "passive"))
      (node (ref "R828") (pin "2") (pinfunction "2_2") (pintype "passive"))
      (node (ref "R834") (pin "2") (pinfunction "2_2") (pintype "passive"))
      (node (ref "R837") (pin "2") (pinfunction "2_2") (pintype "passive"))
      (node (ref "U800") (pin "12") (pinfunction "VDDIO_12") (pintype "passive"))
      (node (ref "U802") (pin "5") (pinfunction "VCC_5") (pintype "passive"))
    )
    (net (code "73") (name "DP3.3VS_PHY") (class "Default")
      (node (ref "C800") (pin "1") (pinfunction "1_1") (pintype "passive"))
      (node (ref "C801") (pin "1") (pinfunction "1_1") (pintype "passive"))
      (node (ref "C802") (pin "1") (pinfunction "1_1") (pintype "passive"))
      (node (ref "C813") (pin "1") (pinfunction "1_1") (pintype "passive"))
      (node (ref "C814") (pin "1") (pinfunction "1_1") (pintype "passive"))
      (node (ref "FB800") (pin "2") (pinfunction "2_2") (pintype "passive"))
      (node (ref "R836") (pin "2") (pinfunction "2_2") (pintype "passive"))
      (node (ref "R839") (pin "2") (pinfunction "2_2") (pintype "passive"))
      (node (ref "R840") (pin "2") (pinfunction "2_2") (pintype "passive"))
      (node (ref "R841") (pin "2") (pinfunction "2_2") (pintype "passive"))
      (node (ref "R842") (pin "2") (pinfunction "2_2") (pintype "passive"))
      (node (ref "U800") (pin "1") (pinfunction "VDD2A_1") (pintype "passive"))
      (node (ref "U800") (pin "27") (pinfunction "VDD1A_27") (pintype "passive"))
    )
    (net (code "74") (name "Net-(CN800-GR_K)") (class "Default")
      (node (ref "CN800") (pin "10") (pinfunction "GR_K_10") (pintype "passive"))
      (node (ref "R849") (pin "2") (pinfunction "2_2") (pintype "passive"))
    )
    (net (code "75") (name "Net-(CN800-YEL_K)") (class "Default")
      (node (ref "CN800") (pin "11") (pinfunction "YEL_K_11") (pintype "passive"))
      (node (ref "R850") (pin "2") (pinfunction "2_2") (pintype "passive"))
    )
    (net (code "76") (name "Net-(LED800-BLUE)") (class "Default")
      (node (ref "LED800") (pin "3") (pinfunction "BLUE_3") (pintype "passive"))
      (node (ref "R833") (pin "1") (pinfunction "1_1") (pintype "passive"))
    )
    (net (code "77") (name "Net-(LED800-GREEN)") (class "Default")
      (node (ref "LED800") (pin "2") (pinfunction "GREEN_2") (pintype "passive"))
      (node (ref "R835") (pin "1") (pinfunction "1_1") (pintype "passive"))
    )
    (net (code "78") (name "Net-(LED800-RED)") (class "Default")
      (node (ref "LED800") (pin "1") (pinfunction "RED_1") (pintype "passive"))
      (node (ref "R838") (pin "1") (pinfunction "1_1") (pintype "passive"))
    )
    (net (code "79") (name "Net-(Q800-G)") (class "Default")
      (node (ref "Q800") (pin "1") (pinfunction "G_1") (pintype "passive"))
      (node (ref "R847") (pin "1") (pinfunction "1_1") (pintype "passive"))
      (node (ref "R848") (pin "2") (pinfunction "2_2") (pintype "passive"))
    )
    (net (code "80") (name "Net-(Q801-G)") (class "Default")
      (node (ref "Q801") (pin "1") (pinfunction "G_1") (pintype "passive"))
      (node (ref "R851") (pin "1") (pinfunction "1_1") (pintype "passive"))
      (node (ref "R852") (pin "2") (pinfunction "2_2") (pintype "passive"))
    )
    (net (code "81") (name "Net-(Q802-G)") (class "Default")
      (node (ref "Q802") (pin "1") (pinfunction "G_1") (pintype "passive"))
      (node (ref "R853") (pin "1") (pinfunction "1_1") (pintype "passive"))
      (node (ref "R854") (pin "2") (pinfunction "2_2") (pintype "passive"))
    )
    (net (code "82") (name "Net-(R822-Pad2)") (class "Default")
      (node (ref "R822") (pin "2") (pinfunction "2_2") (pintype "passive"))
      (node (ref "R823") (pin "2") (pinfunction "2_2") (pintype "passive"))
    )
    (net (code "83") (name "unconnected-(CN800-NC-Pad7)") (class "Default")
      (node (ref "CN800") (pin "7") (pinfunction "NC_7") (pintype "passive+no_connect"))
    )
  )
)
